# main_schematic.net
KiCad netlist of a schematic drawn in Altium Designer
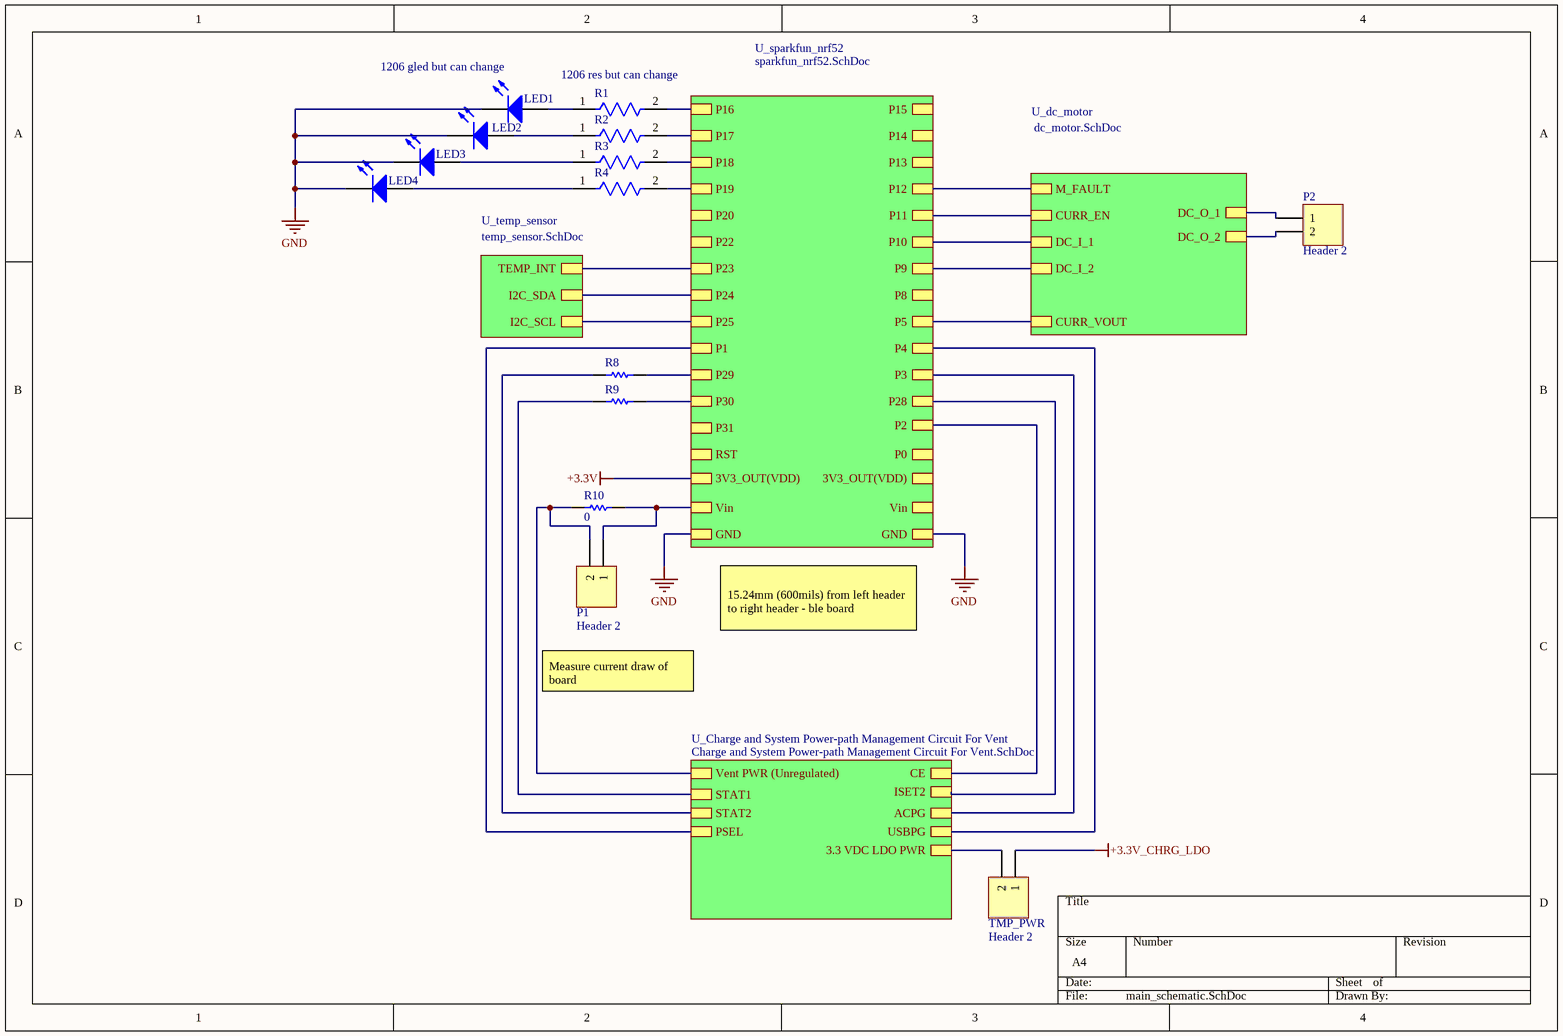
[diagram p0: main_schematic.SchDoc]

(export (version "E")
  (design (tool "Eeschema 10.0.6"))
  (components
    (comp (ref "LED1")
      (value "~")
      (footprint "1206_A")
      (description "QTLP650C4TR\r\n1206 green led")
      (fields (field (name "PARTNUMBER") "150120VS75000") (field (name "MANUFACTURER") "Wuerth Elektronik"))
      (libsource (lib "Altium Content Vault") (part "WE-LED_K1A2-2"))
    )
    (comp (ref "LED2")
      (value "~")
      (footprint "1206_A")
      (description "QTLP650C4TR\r\n1206 green led")
      (fields (field (name "PARTNUMBER") "150120VS75000") (field (name "MANUFACTURER") "Wuerth Elektronik"))
      (libsource (lib "Altium Content Vault") (part "WE-LED_K1A2-2"))
    )
    (comp (ref "LED3")
      (value "~")
      (footprint "1206_A")
      (description "QTLP650C4TR\r\n1206 green led")
      (fields (field (name "PARTNUMBER") "150120VS75000") (field (name "MANUFACTURER") "Wuerth Elektronik"))
      (libsource (lib "Altium Content Vault") (part "WE-LED_K1A2-2"))
    )
    (comp (ref "LED4")
      (value "~")
      (footprint "1206_A")
      (description "QTLP650C4TR\r\n1206 green led")
      (fields (field (name "PARTNUMBER") "150120VS75000") (field (name "MANUFACTURER") "Wuerth Elektronik"))
      (libsource (lib "Altium Content Vault") (part "WE-LED_K1A2-2"))
    )
    (comp (ref "P1")
      (value "Header 2")
      (footprint "HDR1X2")
      (description "Header, 2-Pin")
      (fields (field (name "PUBLISHER") "Altium Limited"))
      (libsource (lib "Miscellaneous Connectors") (part "Header 2"))
    )
    (comp (ref "P2")
      (value "Header 2")
      (footprint "HDR1X2")
      (description "Header, 2-Pin")
      (fields (field (name "PUBLISHER") "Altium Limited"))
      (libsource (lib "") (part "Header 2_1"))
    )
    (comp (ref "R1")
      (value "~")
      (footprint "FP-RC1206-MFG")
      (description "360 ohms resistor \r\n1206 package")
      (fields
        (field (name "MANUFACTURER PART NUMBER") "RC1206JR-070RL")
        (field (name "MANUFACTURER") "YAGEO")
      )
      (libsource (lib "Altium Content Vault") (part "1029c3af85768c4190bb7ad29bc67b5"))
    )
    (comp (ref "R2")
      (value "~")
      (footprint "FP-RC1206-MFG")
      (description "360 ohms resistor \r\n1206 package")
      (fields
        (field (name "MANUFACTURER PART NUMBER") "RC1206JR-070RL")
        (field (name "MANUFACTURER") "YAGEO")
      )
      (libsource (lib "Altium Content Vault") (part "1029c3af85768c4190bb7ad29bc67b5"))
    )
    (comp (ref "R3")
      (value "~")
      (footprint "FP-RC1206-MFG")
      (description "360 ohms resistor \r\n1206 package")
      (fields
        (field (name "MANUFACTURER PART NUMBER") "RC1206JR-070RL")
        (field (name "MANUFACTURER") "YAGEO")
      )
      (libsource (lib "Altium Content Vault") (part "1029c3af85768c4190bb7ad29bc67b5"))
    )
    (comp (ref "R4")
      (value "~")
      (footprint "FP-RC1206-MFG")
      (description "360 ohms resistor \r\n1206 package")
      (fields
        (field (name "MANUFACTURER PART NUMBER") "RC1206JR-070RL")
        (field (name "MANUFACTURER") "YAGEO")
      )
      (libsource (lib "Altium Content Vault") (part "1029c3af85768c4190bb7ad29bc67b5"))
    )
    (comp (ref "R8")
      (value "RC0805FR-0710KL")
      (footprint "RESC2013X60X35NL10T20")
      (description "Chip Resistor, 10 KOhm, +/- 1%, 0.125 W, -55 to 155 degC, 0805 (2012 Metric), RoHS, Tape and Reel")
      (fields (field (name "MANUFACTURER") "Yageo"))
      (libsource (lib "Altium Content Vault") (part "RES-2"))
    )
    (comp (ref "R9")
      (value "RC0805FR-0710KL")
      (footprint "RESC2013X60X35NL10T20")
      (description "Chip Resistor, 10 KOhm, +/- 1%, 0.125 W, -55 to 155 degC, 0805 (2012 Metric), RoHS, Tape and Reel")
      (fields (field (name "MANUFACTURER") "Yageo"))
      (libsource (lib "Altium Content Vault") (part "RES-2"))
    )
    (comp (ref "R10")
      (value "0")
      (footprint "RESC2013X70X40LL20T20")
      (description "2012")
      (fields (field (name "PART NUMBER") "ERJ-6GEYJ471V") (field (name "MANUFACTURER") "Panasonic"))
      (libsource (lib "Altium Content Vault") (part "RES"))
    )
    (comp (ref "TMP_PWR")
      (value "Header 2")
      (footprint "HDR1X2")
      (description "Header, 2-Pin")
      (fields (field (name "PUBLISHER") "Altium Limited"))
      (libsource (lib "Miscellaneous Connectors") (part "Header 2"))
    )
  )
  (nets
    (net (code "2") (name "+3.3V_CHRG_LDO") (class "Default")
      (node (ref "TMP_PWR") (pin "1") (pinfunction "1_1") (pintype "passive"))
    )
    (net (code "3") (name "/3.3 VDC LDO PWR") (class "Default")
      (node (ref "TMP_PWR") (pin "2") (pinfunction "2_2") (pintype "passive"))
    )
    (net (code "11") (name "/DC_O_1") (class "Default")
      (node (ref "P2") (pin "1") (pinfunction "1_1") (pintype "passive"))
    )
    (net (code "12") (name "/DC_O_2") (class "Default")
      (node (ref "P2") (pin "2") (pinfunction "2_2") (pintype "passive"))
    )
    (net (code "24") (name "/P16") (class "Default")
      (node (ref "R1") (pin "2") (pinfunction "2_2") (pintype "passive"))
    )
    (net (code "25") (name "/P17") (class "Default")
      (node (ref "R2") (pin "2") (pinfunction "2_2") (pintype "passive"))
    )
    (net (code "26") (name "/P18") (class "Default")
      (node (ref "R3") (pin "2") (pinfunction "2_2") (pintype "passive"))
    )
    (net (code "27") (name "/P19") (class "Default")
      (node (ref "R4") (pin "2") (pinfunction "2_2") (pintype "passive"))
    )
    (net (code "31") (name "/P29") (class "Default")
      (node (ref "R8") (pin "2") (pinfunction "2_2") (pintype "passive"))
    )
    (net (code "32") (name "/P30") (class "Default")
      (node (ref "R9") (pin "2") (pinfunction "2_2") (pintype "passive"))
    )
    (net (code "35") (name "/STAT1") (class "Default")
      (node (ref "R9") (pin "1") (pinfunction "1_1") (pintype "passive"))
    )
    (net (code "36") (name "/STAT2") (class "Default")
      (node (ref "R8") (pin "1") (pinfunction "1_1") (pintype "passive"))
    )
    (net (code "37") (name "/Vent PWR (Unregulated)") (class "Default")
      (node (ref "P1") (pin "2") (pinfunction "2_2") (pintype "passive"))
      (node (ref "R10") (pin "2") (pinfunction "2_2") (pintype "passive"))
    )
    (net (code "39") (name "/Vin_1") (class "Default")
      (node (ref "P1") (pin "1") (pinfunction "1_1") (pintype "passive"))
      (node (ref "R10") (pin "1") (pinfunction "1_1") (pintype "passive"))
    )
    (net (code "40") (name "GND") (class "Default")
      (node (ref "LED1") (pin "1") (pinfunction "K_1") (pintype "passive"))
      (node (ref "LED2") (pin "1") (pinfunction "K_1") (pintype "passive"))
      (node (ref "LED3") (pin "1") (pinfunction "K_1") (pintype "passive"))
      (node (ref "LED4") (pin "1") (pinfunction "K_1") (pintype "passive"))
    )
    (net (code "41") (name "Net-(LED1-A)") (class "Default")
      (node (ref "LED1") (pin "2") (pinfunction "A_2") (pintype "passive"))
      (node (ref "R1") (pin "1") (pinfunction "1_1") (pintype "passive"))
    )
    (net (code "42") (name "Net-(LED2-A)") (class "Default")
      (node (ref "LED2") (pin "2") (pinfunction "A_2") (pintype "passive"))
      (node (ref "R2") (pin "1") (pinfunction "1_1") (pintype "passive"))
    )
    (net (code "43") (name "Net-(LED3-A)") (class "Default")
      (node (ref "LED3") (pin "2") (pinfunction "A_2") (pintype "passive"))
      (node (ref "R3") (pin "1") (pinfunction "1_1") (pintype "passive"))
    )
    (net (code "44") (name "Net-(LED4-A)") (class "Default")
      (node (ref "LED4") (pin "2") (pinfunction "A_2") (pintype "passive"))
      (node (ref "R4") (pin "1") (pinfunction "1_1") (pintype "passive"))
    )
  )
)
